# differential_led_board.net
KiCad netlist of a schematic drawn in EAGLE
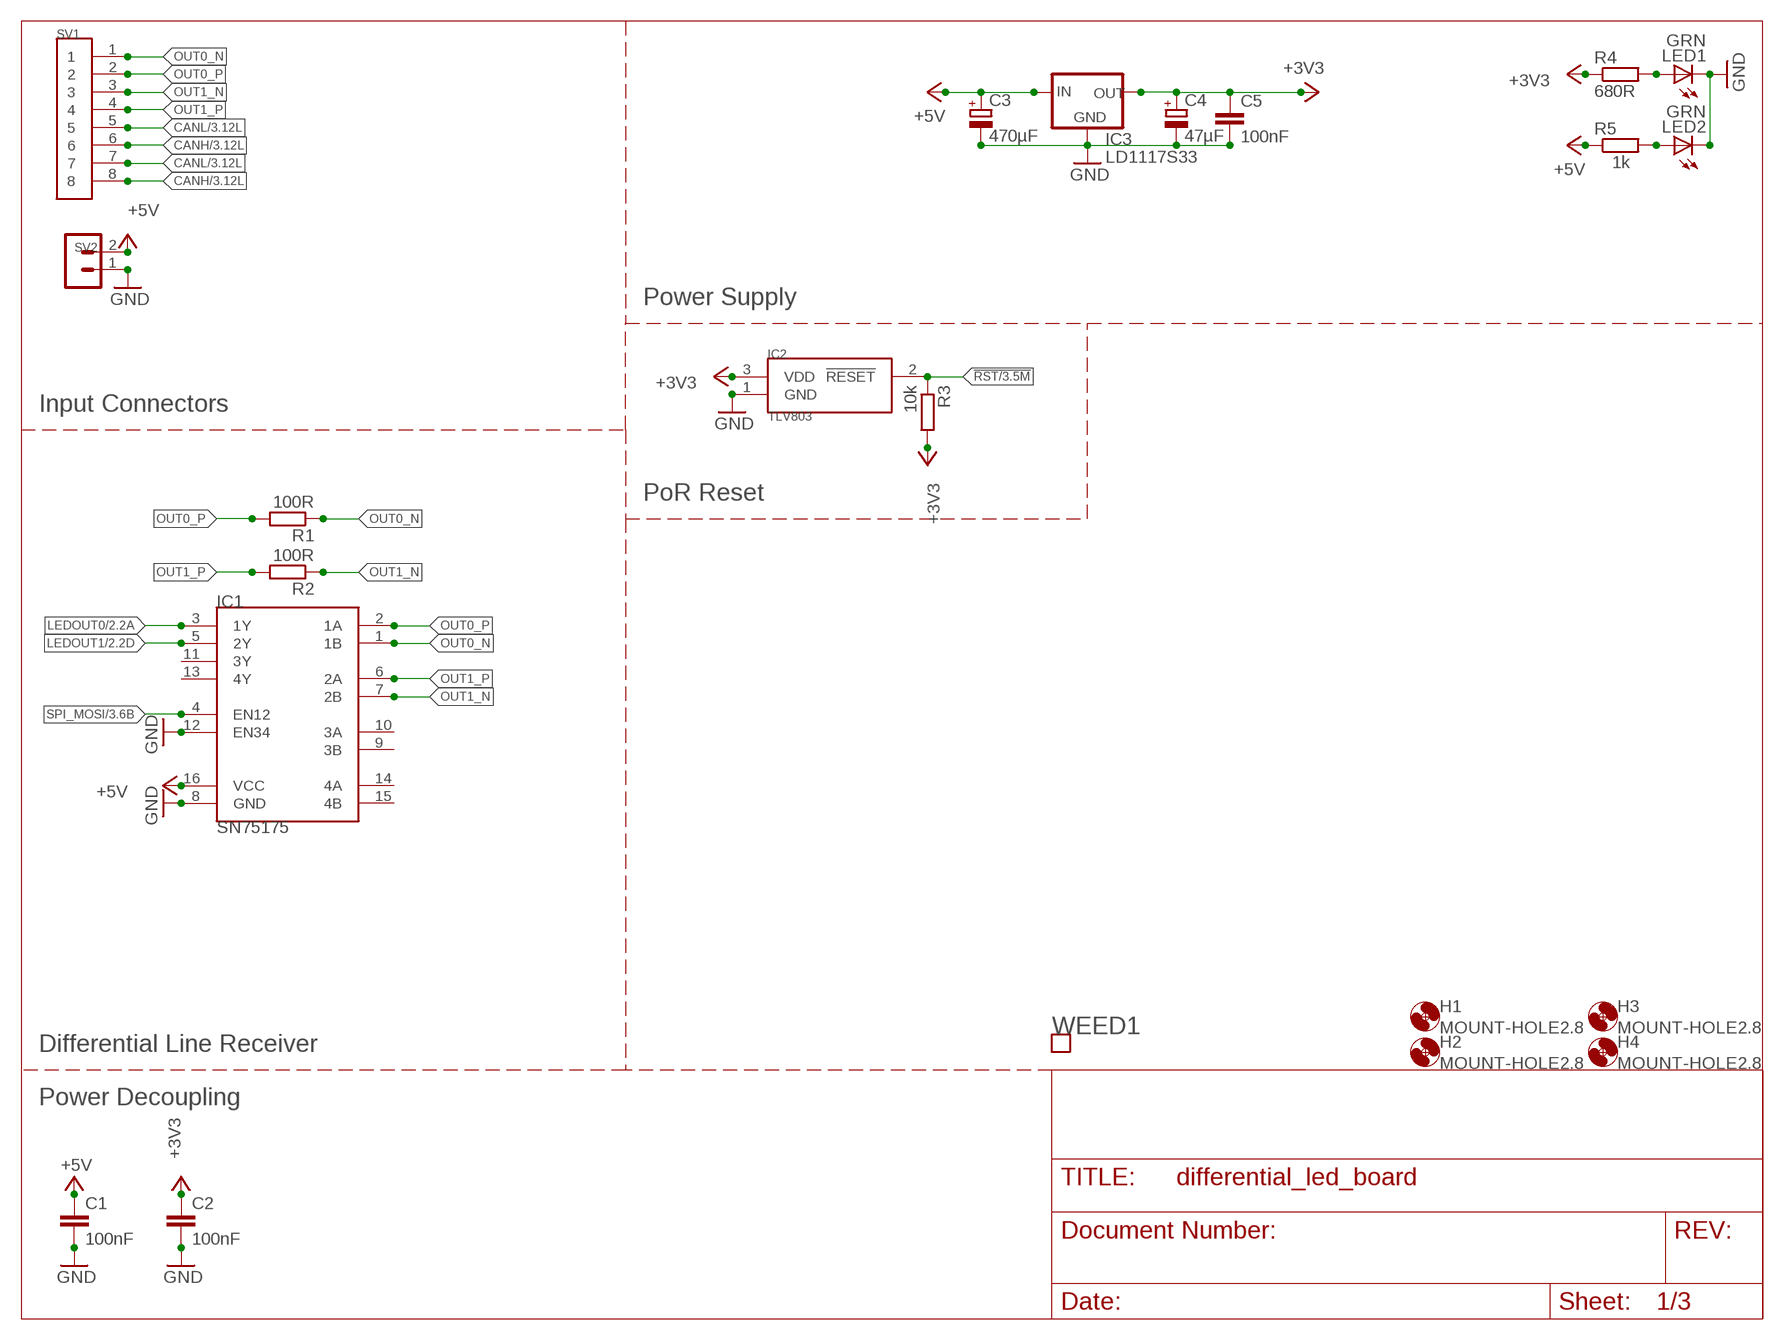
[diagram p0: schematic, sheet 1]
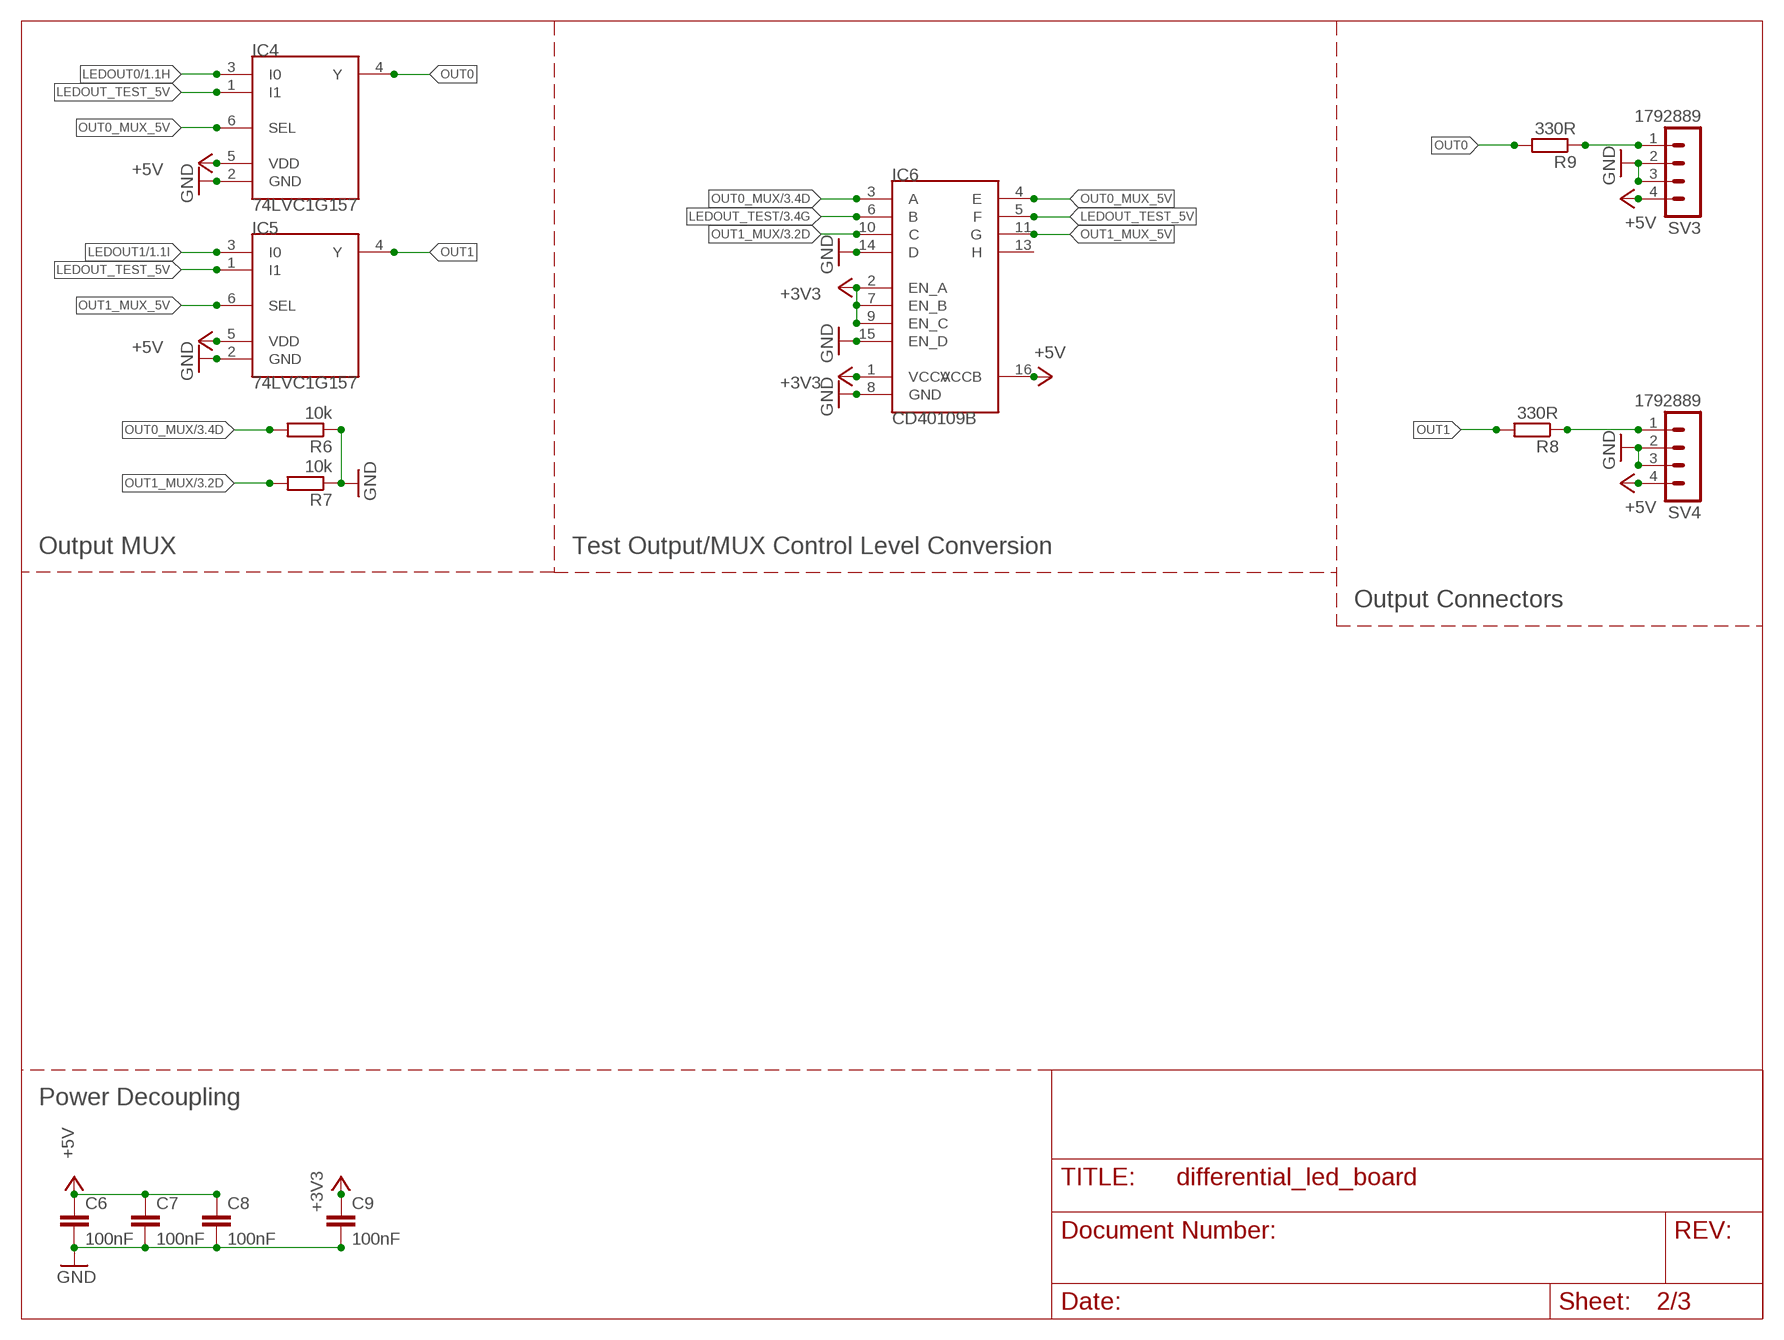
[diagram p1: schematic, sheet 2]
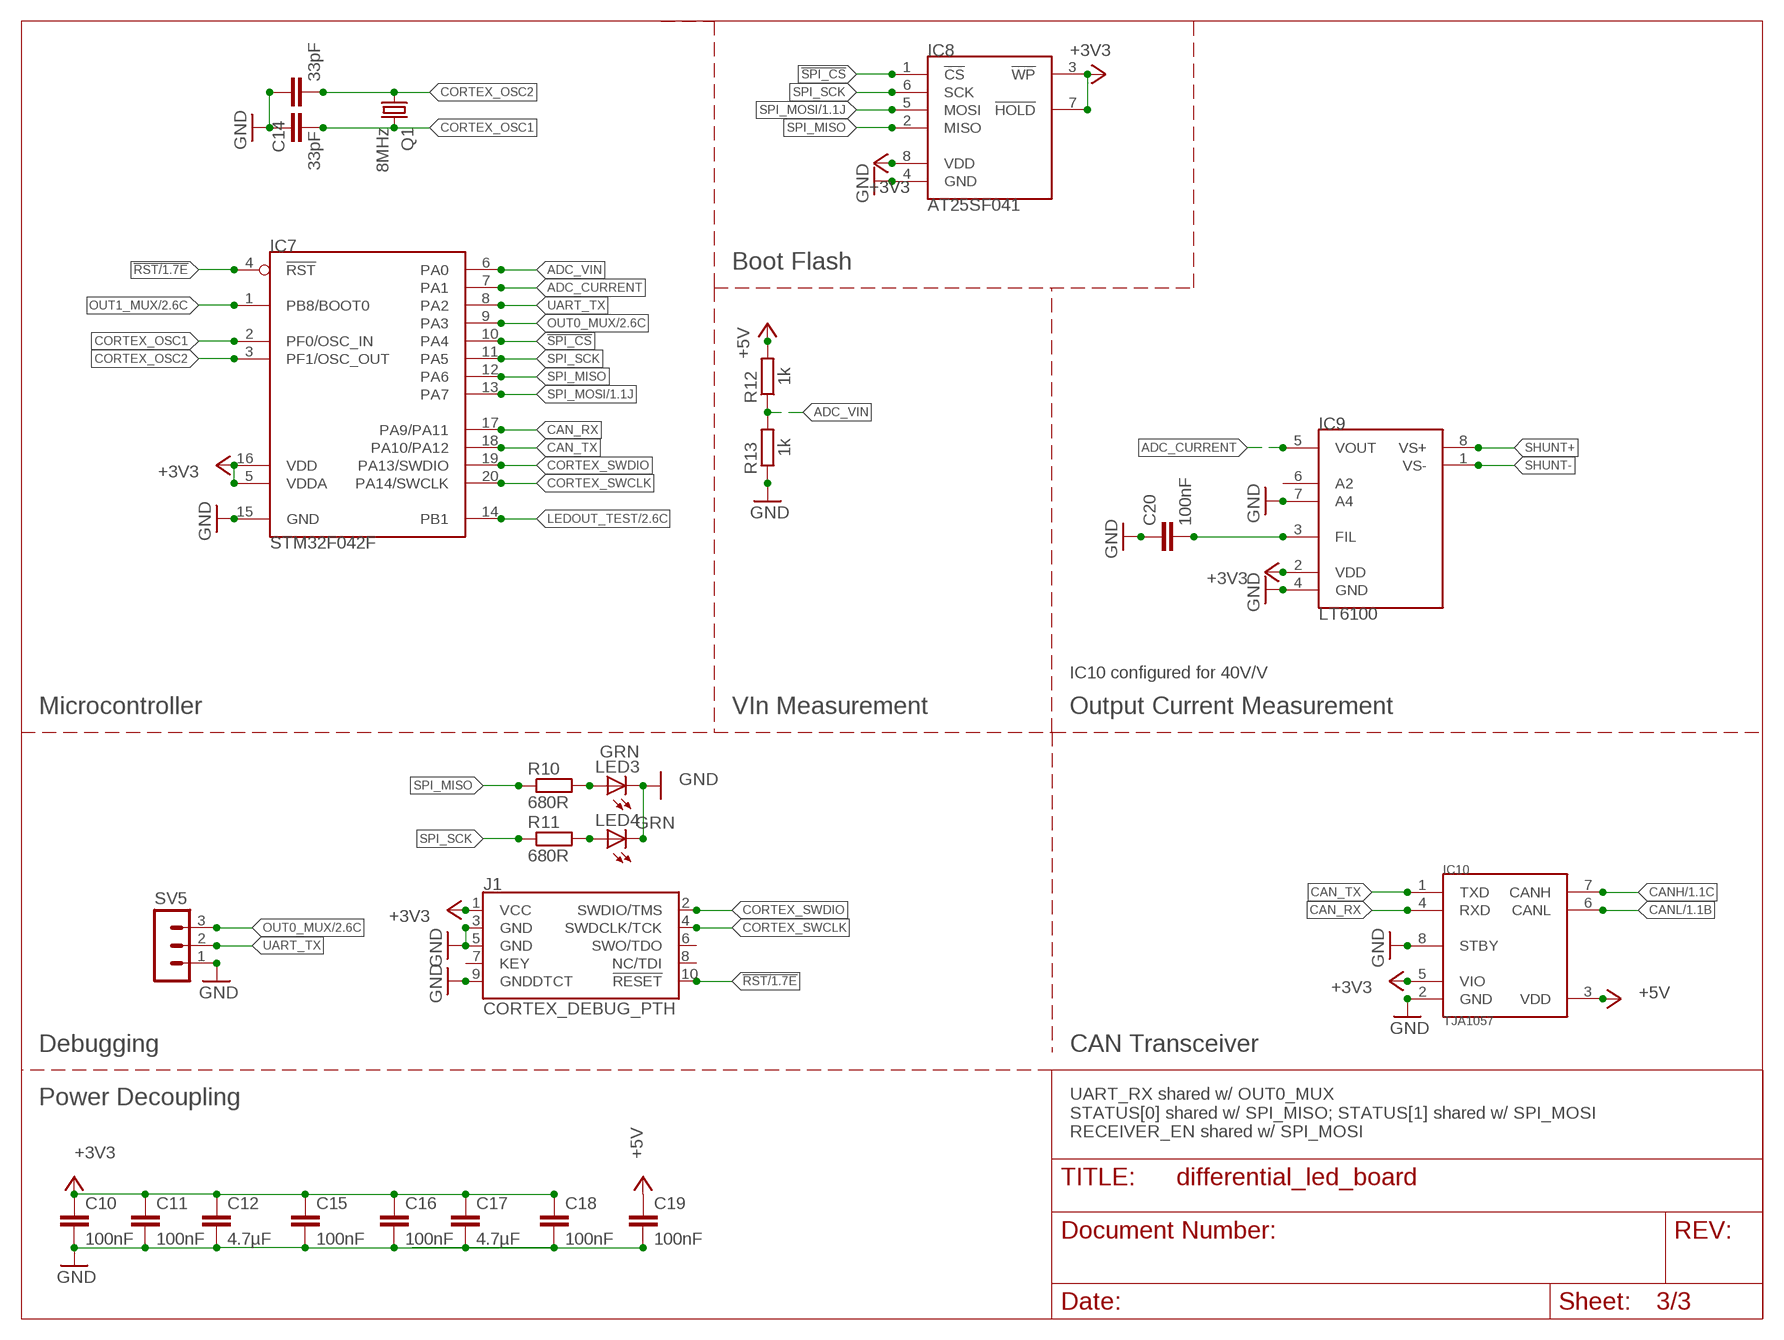
[diagram p2: schematic, sheet 3]

(export (version "E")
  (design (tool "Eeschema 10.0.6"))
  (components
    (comp (ref "C1")
      (value "100nF")
      (footprint "eagle-import:C0805")
      (libsource (lib "eagle-import") (part "C-EUC0805"))
    )
    (comp (ref "C2")
      (value "100nF")
      (footprint "eagle-import:C0805")
      (libsource (lib "eagle-import") (part "C-EUC0805"))
    )
    (comp (ref "C3")
      (value "470µF")
      (footprint "eagle-import:UD-8X10_NICHICON")
      (libsource (lib "eagle-import") (part "CPOL-EUUD-8X10"))
    )
    (comp (ref "C4")
      (value "47µF")
      (footprint "eagle-import:CT6032")
      (libsource (lib "eagle-import") (part "CPOL-EUCT6032"))
    )
    (comp (ref "C5")
      (value "100nF")
      (footprint "eagle-import:C0805")
      (libsource (lib "eagle-import") (part "C-EUC0805"))
    )
    (comp (ref "H1")
      (value "MOUNT-HOLE2.8")
      (footprint "eagle-import:2,8")
      (libsource (lib "eagle-import") (part "MOUNT-HOLE2.8"))
    )
    (comp (ref "H2")
      (value "MOUNT-HOLE2.8")
      (footprint "eagle-import:2,8")
      (libsource (lib "eagle-import") (part "MOUNT-HOLE2.8"))
    )
    (comp (ref "H3")
      (value "MOUNT-HOLE2.8")
      (footprint "eagle-import:2,8")
      (libsource (lib "eagle-import") (part "MOUNT-HOLE2.8"))
    )
    (comp (ref "H4")
      (value "MOUNT-HOLE2.8")
      (footprint "eagle-import:2,8")
      (libsource (lib "eagle-import") (part "MOUNT-HOLE2.8"))
    )
    (comp (ref "IC1")
      (value "SN75175")
      (footprint "eagle-import:SOP-16")
      (libsource (lib "eagle-import") (part "SN75175SOP-16"))
    )
    (comp (ref "IC2")
      (value "TLV803")
      (footprint "eagle-import:SOT23")
      (libsource (lib "eagle-import") (part "TLV803SOT-23"))
    )
    (comp (ref "IC3")
      (value "LD1117S33")
      (footprint "eagle-import:SOT223")
      (libsource (lib "eagle-import") (part "LM1117SOT223"))
    )
    (comp (ref "LED1")
      (value "GRN")
      (footprint "eagle-import:CHIPLED_1206")
      (libsource (lib "eagle-import") (part "LEDCHIPLED_1206"))
    )
    (comp (ref "LED2")
      (value "GRN")
      (footprint "eagle-import:CHIPLED_1206")
      (libsource (lib "eagle-import") (part "LEDCHIPLED_1206"))
    )
    (comp (ref "R1")
      (value "100R")
      (footprint "eagle-import:M1206")
      (libsource (lib "eagle-import") (part "R-EU_M1206"))
    )
    (comp (ref "R2")
      (value "100R")
      (footprint "eagle-import:M1206")
      (libsource (lib "eagle-import") (part "R-EU_M1206"))
    )
    (comp (ref "R3")
      (value "10k")
      (footprint "eagle-import:M0805")
      (libsource (lib "eagle-import") (part "R-EU_M0805"))
    )
    (comp (ref "R4")
      (value "680R")
      (footprint "eagle-import:M0805")
      (libsource (lib "eagle-import") (part "R-EU_M0805"))
    )
    (comp (ref "R5")
      (value "1k")
      (footprint "eagle-import:M0805")
      (libsource (lib "eagle-import") (part "R-EU_M0805"))
    )
    (comp (ref "SV1")
      (value "SS-51000-003")
      (footprint "eagle-import:SS-51000-003")
      (libsource (lib "eagle-import") (part "SS-51000-003"))
    )
    (comp (ref "SV2")
      (value "1792863")
      (footprint "eagle-import:1792863")
      (libsource (lib "eagle-import") (part "1792863"))
    )
    (comp (ref "WEED1")
      (value "WEED")
      (footprint "eagle-import:DOINK")
      (libsource (lib "eagle-import") (part "WEED"))
    )
    (comp (ref "C10")
      (value "100nF")
      (footprint "eagle-import:C0805")
      (libsource (lib "eagle-import") (part "C-EUC0805"))
    )
    (comp (ref "C11")
      (value "100nF")
      (footprint "eagle-import:C0805")
      (libsource (lib "eagle-import") (part "C-EUC0805"))
    )
    (comp (ref "C12")
      (value "4.7µF")
      (footprint "eagle-import:C0805")
      (libsource (lib "eagle-import") (part "C-EUC0805"))
    )
    (comp (ref "C13")
      (value "33pF")
      (footprint "eagle-import:C0805")
      (libsource (lib "eagle-import") (part "C-EUC0805"))
    )
    (comp (ref "C14")
      (value "33pF")
      (footprint "eagle-import:C0805")
      (libsource (lib "eagle-import") (part "C-EUC0805"))
    )
    (comp (ref "C15")
      (value "100nF")
      (footprint "eagle-import:C0805")
      (libsource (lib "eagle-import") (part "C-EUC0805"))
    )
    (comp (ref "C16")
      (value "100nF")
      (footprint "eagle-import:C0805")
      (libsource (lib "eagle-import") (part "C-EUC0805"))
    )
    (comp (ref "C17")
      (value "4.7µF")
      (footprint "eagle-import:C0805")
      (libsource (lib "eagle-import") (part "C-EUC0805"))
    )
    (comp (ref "C18")
      (value "100nF")
      (footprint "eagle-import:C0805")
      (libsource (lib "eagle-import") (part "C-EUC0805"))
    )
    (comp (ref "C19")
      (value "100nF")
      (footprint "eagle-import:C0805")
      (libsource (lib "eagle-import") (part "C-EUC0805"))
    )
    (comp (ref "C20")
      (value "100nF")
      (footprint "eagle-import:C0805")
      (libsource (lib "eagle-import") (part "C-EUC0805"))
    )
    (comp (ref "IC7")
      (value "STM32F042F")
      (footprint "eagle-import:TSSOP20")
      (libsource (lib "eagle-import") (part "STM32F042F"))
    )
    (comp (ref "IC8")
      (value "AT25SF041")
      (footprint "eagle-import:SOIC8")
      (libsource (lib "eagle-import") (part "AT25SF041"))
    )
    (comp (ref "IC9")
      (value "LT6100")
      (footprint "eagle-import:MSOP8")
      (libsource (lib "eagle-import") (part "LT6100MSOP-8"))
    )
    (comp (ref "IC10")
      (value "TJA1057")
      (footprint "eagle-import:SOIC8")
      (libsource (lib "eagle-import") (part "TJA1057"))
    )
    (comp (ref "J1")
      (value "CORTEX_DEBUG_PTH")
      (footprint "eagle-import:2X5-PTH-1.27MM")
      (libsource (lib "eagle-import") (part "CORTEX_DEBUG_PTH"))
    )
    (comp (ref "LED3")
      (value "GRN")
      (footprint "eagle-import:CHIPLED_1206")
      (libsource (lib "eagle-import") (part "LEDCHIPLED_1206"))
    )
    (comp (ref "LED4")
      (value "GRN")
      (footprint "eagle-import:CHIPLED_1206")
      (libsource (lib "eagle-import") (part "LEDCHIPLED_1206"))
    )
    (comp (ref "Q1")
      (value "8MHz")
      (footprint "eagle-import:HC49UP")
      (libsource (lib "eagle-import") (part "CRYSTALHC49UP"))
    )
    (comp (ref "R10")
      (value "680R")
      (footprint "eagle-import:M0805")
      (libsource (lib "eagle-import") (part "R-EU_M0805"))
    )
    (comp (ref "R11")
      (value "680R")
      (footprint "eagle-import:M0805")
      (libsource (lib "eagle-import") (part "R-EU_M0805"))
    )
    (comp (ref "R12")
      (value "1k")
      (footprint "eagle-import:M0805")
      (libsource (lib "eagle-import") (part "R-EU_M0805"))
    )
    (comp (ref "R13")
      (value "1k")
      (footprint "eagle-import:M0805")
      (libsource (lib "eagle-import") (part "R-EU_M0805"))
    )
    (comp (ref "SV5")
      (value "MA03-1")
      (footprint "eagle-import:MA03-1")
      (libsource (lib "eagle-import") (part "MA03-1"))
    )
    (comp (ref "C6")
      (value "100nF")
      (footprint "eagle-import:C0805")
      (libsource (lib "eagle-import") (part "C-EUC0805"))
    )
    (comp (ref "C7")
      (value "100nF")
      (footprint "eagle-import:C0805")
      (libsource (lib "eagle-import") (part "C-EUC0805"))
    )
    (comp (ref "C8")
      (value "100nF")
      (footprint "eagle-import:C0805")
      (libsource (lib "eagle-import") (part "C-EUC0805"))
    )
    (comp (ref "C9")
      (value "100nF")
      (footprint "eagle-import:C0805")
      (libsource (lib "eagle-import") (part "C-EUC0805"))
    )
    (comp (ref "IC4")
      (value "74LVC1G157")
      (footprint "eagle-import:SOT457R_PHILIPS")
      (libsource (lib "eagle-import") (part "74LVC1G157SOT457"))
    )
    (comp (ref "IC5")
      (value "74LVC1G157")
      (footprint "eagle-import:SOT457R_PHILIPS")
      (libsource (lib "eagle-import") (part "74LVC1G157SOT457"))
    )
    (comp (ref "IC6")
      (value "CD40109B")
      (footprint "eagle-import:SO16")
      (libsource (lib "eagle-import") (part "CD40109BSO-16"))
    )
    (comp (ref "R6")
      (value "10k")
      (footprint "eagle-import:M0805")
      (libsource (lib "eagle-import") (part "R-EU_M0805"))
    )
    (comp (ref "R7")
      (value "10k")
      (footprint "eagle-import:M0805")
      (libsource (lib "eagle-import") (part "R-EU_M0805"))
    )
    (comp (ref "R8")
      (value "330R")
      (footprint "eagle-import:M0805")
      (libsource (lib "eagle-import") (part "R-EU_M0805"))
    )
    (comp (ref "R9")
      (value "330R")
      (footprint "eagle-import:M0805")
      (libsource (lib "eagle-import") (part "R-EU_M0805"))
    )
    (comp (ref "SV3")
      (value "1792889")
      (footprint "eagle-import:1792889")
      (libsource (lib "eagle-import") (part "1792889"))
    )
    (comp (ref "SV4")
      (value "1792889")
      (footprint "eagle-import:1792889")
      (libsource (lib "eagle-import") (part "1792889"))
    )
  )
  (nets
    (net (code "1") (name "+3V3") (class "Default")
      (node (ref "C10") (pin "1") (pinfunction "1_1") (pintype "passive"))
      (node (ref "C11") (pin "1") (pinfunction "1_1") (pintype "passive"))
      (node (ref "C12") (pin "1") (pinfunction "1_1") (pintype "passive"))
      (node (ref "C15") (pin "1") (pinfunction "1_1") (pintype "passive"))
      (node (ref "C16") (pin "1") (pinfunction "1_1") (pintype "passive"))
      (node (ref "C17") (pin "1") (pinfunction "1_1") (pintype "passive"))
      (node (ref "C18") (pin "1") (pinfunction "1_1") (pintype "passive"))
      (node (ref "C2") (pin "1") (pinfunction "1_1") (pintype "passive"))
      (node (ref "C4") (pin "+") (pinfunction "+_+") (pintype "passive"))
      (node (ref "C5") (pin "1") (pinfunction "1_1") (pintype "passive"))
      (node (ref "C9") (pin "1") (pinfunction "1_1") (pintype "passive"))
      (node (ref "IC10") (pin "5") (pinfunction "VIO_5") (pintype "bidirectional"))
      (node (ref "IC2") (pin "3") (pinfunction "VDD_3") (pintype "power_in"))
      (node (ref "IC3") (pin "2") (pinfunction "OUT_2") (pintype "output"))
      (node (ref "IC3") (pin "4") (pinfunction "OUT_4") (pintype "output"))
      (node (ref "IC6") (pin "1") (pinfunction "VCCA_1") (pintype "bidirectional"))
      (node (ref "IC6") (pin "2") (pinfunction "EN_A_2") (pintype "bidirectional"))
      (node (ref "IC6") (pin "7") (pinfunction "EN_B_7") (pintype "bidirectional"))
      (node (ref "IC6") (pin "9") (pinfunction "EN_C_9") (pintype "bidirectional"))
      (node (ref "IC7") (pin "16") (pinfunction "VDD_16") (pintype "power_in"))
      (node (ref "IC7") (pin "5") (pinfunction "VDDA_5") (pintype "power_in"))
      (node (ref "IC8") (pin "3") (pinfunction "~{WP}_3") (pintype "bidirectional"))
      (node (ref "IC8") (pin "7") (pinfunction "~{HOLD}_7") (pintype "bidirectional"))
      (node (ref "IC8") (pin "8") (pinfunction "VDD_8") (pintype "power_in"))
      (node (ref "IC9") (pin "2") (pinfunction "VDD_2") (pintype "power_in"))
      (node (ref "J1") (pin "1") (pinfunction "VCC_1") (pintype "bidirectional"))
      (node (ref "R3") (pin "2") (pinfunction "2_2") (pintype "passive"))
      (node (ref "R4") (pin "1") (pinfunction "1_1") (pintype "passive"))
    )
    (net (code "2") (name "+5V") (class "Default")
      (node (ref "C1") (pin "1") (pinfunction "1_1") (pintype "passive"))
      (node (ref "C19") (pin "1") (pinfunction "1_1") (pintype "passive"))
      (node (ref "C3") (pin "+") (pinfunction "+_+") (pintype "passive"))
      (node (ref "C6") (pin "1") (pinfunction "1_1") (pintype "passive"))
      (node (ref "C7") (pin "1") (pinfunction "1_1") (pintype "passive"))
      (node (ref "C8") (pin "1") (pinfunction "1_1") (pintype "passive"))
      (node (ref "IC1") (pin "16") (pinfunction "VCC_16") (pintype "power_in"))
      (node (ref "IC10") (pin "3") (pinfunction "VDD_3") (pintype "bidirectional"))
      (node (ref "IC3") (pin "3") (pinfunction "IN_3") (pintype "input"))
      (node (ref "IC4") (pin "5") (pinfunction "VDD_5") (pintype "power_in"))
      (node (ref "IC5") (pin "5") (pinfunction "VDD_5") (pintype "power_in"))
      (node (ref "IC6") (pin "16") (pinfunction "VCCB_16") (pintype "bidirectional"))
      (node (ref "R12") (pin "2") (pinfunction "2_2") (pintype "passive"))
      (node (ref "R5") (pin "1") (pinfunction "1_1") (pintype "passive"))
      (node (ref "SV2") (pin "2") (pinfunction "2_2") (pintype "passive"))
      (node (ref "SV3") (pin "4") (pinfunction "4_4") (pintype "passive"))
      (node (ref "SV4") (pin "4") (pinfunction "4_4") (pintype "passive"))
    )
    (net (code "3") (name "ADC_CURRENT") (class "Default")
      (node (ref "IC7") (pin "7") (pinfunction "PA1_7") (pintype "bidirectional"))
      (node (ref "IC9") (pin "5") (pinfunction "VOUT_5") (pintype "bidirectional"))
    )
    (net (code "4") (name "ADC_VIN") (class "Default")
      (node (ref "IC7") (pin "6") (pinfunction "PA0_6") (pintype "bidirectional"))
      (node (ref "R12") (pin "1") (pinfunction "1_1") (pintype "passive"))
      (node (ref "R13") (pin "2") (pinfunction "2_2") (pintype "passive"))
    )
    (net (code "5") (name "CANH") (class "Default")
      (node (ref "IC10") (pin "7") (pinfunction "CANH_7") (pintype "bidirectional"))
      (node (ref "SV1") (pin "6") (pinfunction "6_6") (pintype "passive"))
      (node (ref "SV1") (pin "8") (pinfunction "8_8") (pintype "passive"))
    )
    (net (code "6") (name "CANL") (class "Default")
      (node (ref "IC10") (pin "6") (pinfunction "CANL_6") (pintype "bidirectional"))
      (node (ref "SV1") (pin "5") (pinfunction "5_5") (pintype "passive"))
      (node (ref "SV1") (pin "7") (pinfunction "7_7") (pintype "passive"))
    )
    (net (code "7") (name "CAN_RX") (class "Default")
      (node (ref "IC10") (pin "4") (pinfunction "RXD_4") (pintype "bidirectional"))
      (node (ref "IC7") (pin "17") (pinfunction "PA9/PA11_17") (pintype "bidirectional"))
    )
    (net (code "8") (name "CAN_TX") (class "Default")
      (node (ref "IC10") (pin "1") (pinfunction "TXD_1") (pintype "bidirectional"))
      (node (ref "IC7") (pin "18") (pinfunction "PA10/PA12_18") (pintype "bidirectional"))
    )
    (net (code "9") (name "CORTEX_OSC1") (class "Default")
      (node (ref "C14") (pin "2") (pinfunction "2_2") (pintype "passive"))
      (node (ref "IC7") (pin "2") (pinfunction "PF0/OSC_IN_2") (pintype "bidirectional"))
      (node (ref "Q1") (pin "2") (pinfunction "2_2") (pintype "passive"))
    )
    (net (code "10") (name "CORTEX_OSC2") (class "Default")
      (node (ref "C13") (pin "2") (pinfunction "2_2") (pintype "passive"))
      (node (ref "IC7") (pin "3") (pinfunction "PF1/OSC_OUT_3") (pintype "bidirectional"))
      (node (ref "Q1") (pin "1") (pinfunction "1_1") (pintype "passive"))
    )
    (net (code "11") (name "CORTEX_SWCLK") (class "Default")
      (node (ref "IC7") (pin "20") (pinfunction "PA14/SWCLK_20") (pintype "bidirectional"))
      (node (ref "J1") (pin "4") (pinfunction "SWDCLK/TCK_4") (pintype "bidirectional"))
    )
    (net (code "12") (name "CORTEX_SWDIO") (class "Default")
      (node (ref "IC7") (pin "19") (pinfunction "PA13/SWDIO_19") (pintype "bidirectional"))
      (node (ref "J1") (pin "2") (pinfunction "SWDIO/TMS_2") (pintype "bidirectional"))
    )
    (net (code "13") (name "GND") (class "Default")
      (node (ref "C1") (pin "2") (pinfunction "2_2") (pintype "passive"))
      (node (ref "C10") (pin "2") (pinfunction "2_2") (pintype "passive"))
      (node (ref "C11") (pin "2") (pinfunction "2_2") (pintype "passive"))
      (node (ref "C12") (pin "2") (pinfunction "2_2") (pintype "passive"))
      (node (ref "C13") (pin "1") (pinfunction "1_1") (pintype "passive"))
      (node (ref "C14") (pin "1") (pinfunction "1_1") (pintype "passive"))
      (node (ref "C15") (pin "2") (pinfunction "2_2") (pintype "passive"))
      (node (ref "C16") (pin "2") (pinfunction "2_2") (pintype "passive"))
      (node (ref "C17") (pin "2") (pinfunction "2_2") (pintype "passive"))
      (node (ref "C18") (pin "2") (pinfunction "2_2") (pintype "passive"))
      (node (ref "C19") (pin "2") (pinfunction "2_2") (pintype "passive"))
      (node (ref "C2") (pin "2") (pinfunction "2_2") (pintype "passive"))
      (node (ref "C20") (pin "1") (pinfunction "1_1") (pintype "passive"))
      (node (ref "C3") (pin "-") (pinfunction "-_-") (pintype "passive"))
      (node (ref "C4") (pin "-") (pinfunction "-_-") (pintype "passive"))
      (node (ref "C5") (pin "2") (pinfunction "2_2") (pintype "passive"))
      (node (ref "C6") (pin "2") (pinfunction "2_2") (pintype "passive"))
      (node (ref "C7") (pin "2") (pinfunction "2_2") (pintype "passive"))
      (node (ref "C8") (pin "2") (pinfunction "2_2") (pintype "passive"))
      (node (ref "C9") (pin "2") (pinfunction "2_2") (pintype "passive"))
      (node (ref "IC1") (pin "12") (pinfunction "EN34_12") (pintype "input"))
      (node (ref "IC1") (pin "8") (pinfunction "GND_8") (pintype "power_in"))
      (node (ref "IC10") (pin "2") (pinfunction "GND_2") (pintype "bidirectional"))
      (node (ref "IC10") (pin "8") (pinfunction "STBY_8") (pintype "bidirectional"))
      (node (ref "IC2") (pin "1") (pinfunction "GND_1") (pintype "power_in"))
      (node (ref "IC3") (pin "1") (pinfunction "GND_1") (pintype "input"))
      (node (ref "IC4") (pin "2") (pinfunction "GND_2") (pintype "power_in"))
      (node (ref "IC5") (pin "2") (pinfunction "GND_2") (pintype "power_in"))
      (node (ref "IC6") (pin "14") (pinfunction "D_14") (pintype "bidirectional"))
      (node (ref "IC6") (pin "15") (pinfunction "EN_D_15") (pintype "bidirectional"))
      (node (ref "IC6") (pin "8") (pinfunction "GND_8") (pintype "bidirectional"))
      (node (ref "IC7") (pin "15") (pinfunction "GND_15") (pintype "power_in"))
      (node (ref "IC8") (pin "4") (pinfunction "GND_4") (pintype "power_in"))
      (node (ref "IC9") (pin "4") (pinfunction "GND_4") (pintype "power_in"))
      (node (ref "IC9") (pin "7") (pinfunction "A4_7") (pintype "bidirectional"))
      (node (ref "J1") (pin "3") (pinfunction "GND_3") (pintype "bidirectional"))
      (node (ref "J1") (pin "5") (pinfunction "GND_5") (pintype "bidirectional"))
      (node (ref "J1") (pin "9") (pinfunction "GNDDTCT_9") (pintype "bidirectional"))
      (node (ref "LED1") (pin "C") (pinfunction "C_C") (pintype "passive"))
      (node (ref "LED2") (pin "C") (pinfunction "C_C") (pintype "passive"))
      (node (ref "LED3") (pin "C") (pinfunction "C_C") (pintype "passive"))
      (node (ref "LED4") (pin "C") (pinfunction "C_C") (pintype "passive"))
      (node (ref "R13") (pin "1") (pinfunction "1_1") (pintype "passive"))
      (node (ref "R6") (pin "1") (pinfunction "1_1") (pintype "passive"))
      (node (ref "R7") (pin "1") (pinfunction "1_1") (pintype "passive"))
      (node (ref "SV2") (pin "1") (pinfunction "1_1") (pintype "passive"))
      (node (ref "SV3") (pin "2") (pinfunction "2_2") (pintype "passive"))
      (node (ref "SV3") (pin "3") (pinfunction "3_3") (pintype "passive"))
      (node (ref "SV4") (pin "2") (pinfunction "2_2") (pintype "passive"))
      (node (ref "SV4") (pin "3") (pinfunction "3_3") (pintype "passive"))
      (node (ref "SV5") (pin "1") (pinfunction "1_1") (pintype "passive"))
    )
    (net (code "14") (name "LEDOUT0") (class "Default")
      (node (ref "IC1") (pin "3") (pinfunction "1Y_3") (pintype "output"))
      (node (ref "IC4") (pin "3") (pinfunction "I0_3") (pintype "input"))
    )
    (net (code "15") (name "LEDOUT1") (class "Default")
      (node (ref "IC1") (pin "5") (pinfunction "2Y_5") (pintype "output"))
      (node (ref "IC5") (pin "3") (pinfunction "I0_3") (pintype "input"))
    )
    (net (code "16") (name "LEDOUT_TEST") (class "Default")
      (node (ref "IC6") (pin "6") (pinfunction "B_6") (pintype "bidirectional"))
      (node (ref "IC7") (pin "14") (pinfunction "PB1_14") (pintype "bidirectional"))
    )
    (net (code "17") (name "LEDOUT_TEST_5V") (class "Default")
      (node (ref "IC4") (pin "1") (pinfunction "I1_1") (pintype "input"))
      (node (ref "IC5") (pin "1") (pinfunction "I1_1") (pintype "input"))
      (node (ref "IC6") (pin "5") (pinfunction "F_5") (pintype "bidirectional"))
    )
    (net (code "18") (name "Net-(IC9-FIL)") (class "Default")
      (node (ref "C20") (pin "2") (pinfunction "2_2") (pintype "passive"))
      (node (ref "IC9") (pin "3") (pinfunction "FIL_3") (pintype "bidirectional"))
    )
    (net (code "19") (name "Net-(LED1-PadA)") (class "Default")
      (node (ref "LED1") (pin "A") (pinfunction "A_A") (pintype "passive"))
      (node (ref "R4") (pin "2") (pinfunction "2_2") (pintype "passive"))
    )
    (net (code "20") (name "Net-(LED2-PadA)") (class "Default")
      (node (ref "LED2") (pin "A") (pinfunction "A_A") (pintype "passive"))
      (node (ref "R5") (pin "2") (pinfunction "2_2") (pintype "passive"))
    )
    (net (code "21") (name "Net-(LED3-PadA)") (class "Default")
      (node (ref "LED3") (pin "A") (pinfunction "A_A") (pintype "passive"))
      (node (ref "R10") (pin "2") (pinfunction "2_2") (pintype "passive"))
    )
    (net (code "22") (name "Net-(LED4-PadA)") (class "Default")
      (node (ref "LED4") (pin "A") (pinfunction "A_A") (pintype "passive"))
      (node (ref "R11") (pin "2") (pinfunction "2_2") (pintype "passive"))
    )
    (net (code "23") (name "Net-(R8-Pad1)") (class "Default")
      (node (ref "R8") (pin "1") (pinfunction "1_1") (pintype "passive"))
      (node (ref "SV4") (pin "1") (pinfunction "1_1") (pintype "passive"))
    )
    (net (code "24") (name "Net-(R9-Pad1)") (class "Default")
      (node (ref "R9") (pin "1") (pinfunction "1_1") (pintype "passive"))
      (node (ref "SV3") (pin "1") (pinfunction "1_1") (pintype "passive"))
    )
    (net (code "25") (name "OUT0") (class "Default")
      (node (ref "IC4") (pin "4") (pinfunction "Y_4") (pintype "output"))
      (node (ref "R9") (pin "2") (pinfunction "2_2") (pintype "passive"))
    )
    (net (code "26") (name "OUT0_MUX") (class "Default")
      (node (ref "IC6") (pin "3") (pinfunction "A_3") (pintype "bidirectional"))
      (node (ref "IC7") (pin "9") (pinfunction "PA3_9") (pintype "bidirectional"))
      (node (ref "R6") (pin "2") (pinfunction "2_2") (pintype "passive"))
      (node (ref "SV5") (pin "3") (pinfunction "3_3") (pintype "passive"))
    )
    (net (code "27") (name "OUT0_MUX_5V") (class "Default")
      (node (ref "IC4") (pin "6") (pinfunction "SEL_6") (pintype "input"))
      (node (ref "IC6") (pin "4") (pinfunction "E_4") (pintype "bidirectional"))
    )
    (net (code "28") (name "OUT0_N") (class "Default")
      (node (ref "IC1") (pin "1") (pinfunction "1B_1") (pintype "bidirectional"))
      (node (ref "R1") (pin "1") (pinfunction "1_1") (pintype "passive"))
      (node (ref "SV1") (pin "1") (pinfunction "1_1") (pintype "passive"))
    )
    (net (code "29") (name "OUT0_P") (class "Default")
      (node (ref "IC1") (pin "2") (pinfunction "1A_2") (pintype "bidirectional"))
      (node (ref "R1") (pin "2") (pinfunction "2_2") (pintype "passive"))
      (node (ref "SV1") (pin "2") (pinfunction "2_2") (pintype "passive"))
    )
    (net (code "30") (name "OUT1") (class "Default")
      (node (ref "IC5") (pin "4") (pinfunction "Y_4") (pintype "output"))
      (node (ref "R8") (pin "2") (pinfunction "2_2") (pintype "passive"))
    )
    (net (code "31") (name "OUT1_MUX") (class "Default")
      (node (ref "IC6") (pin "10") (pinfunction "C_10") (pintype "bidirectional"))
      (node (ref "IC7") (pin "1") (pinfunction "PB8/BOOT0_1") (pintype "bidirectional"))
      (node (ref "R7") (pin "2") (pinfunction "2_2") (pintype "passive"))
    )
    (net (code "32") (name "OUT1_MUX_5V") (class "Default")
      (node (ref "IC5") (pin "6") (pinfunction "SEL_6") (pintype "input"))
      (node (ref "IC6") (pin "11") (pinfunction "G_11") (pintype "bidirectional"))
    )
    (net (code "33") (name "OUT1_N") (class "Default")
      (node (ref "IC1") (pin "7") (pinfunction "2B_7") (pintype "bidirectional"))
      (node (ref "R2") (pin "1") (pinfunction "1_1") (pintype "passive"))
      (node (ref "SV1") (pin "3") (pinfunction "3_3") (pintype "passive"))
    )
    (net (code "34") (name "OUT1_P") (class "Default")
      (node (ref "IC1") (pin "6") (pinfunction "2A_6") (pintype "bidirectional"))
      (node (ref "R2") (pin "2") (pinfunction "2_2") (pintype "passive"))
      (node (ref "SV1") (pin "4") (pinfunction "4_4") (pintype "passive"))
    )
    (net (code "35") (name "SHUNT+") (class "Default")
      (node (ref "IC9") (pin "8") (pinfunction "VS+_8") (pintype "bidirectional"))
    )
    (net (code "36") (name "SHUNT-") (class "Default")
      (node (ref "IC9") (pin "1") (pinfunction "VS-_1") (pintype "bidirectional"))
    )
    (net (code "37") (name "SPI_MISO") (class "Default")
      (node (ref "IC7") (pin "12") (pinfunction "PA6_12") (pintype "bidirectional"))
      (node (ref "IC8") (pin "2") (pinfunction "MISO_2") (pintype "bidirectional"))
      (node (ref "R10") (pin "1") (pinfunction "1_1") (pintype "passive"))
    )
    (net (code "38") (name "SPI_MOSI") (class "Default")
      (node (ref "IC1") (pin "4") (pinfunction "EN12_4") (pintype "input"))
      (node (ref "IC7") (pin "13") (pinfunction "PA7_13") (pintype "bidirectional"))
      (node (ref "IC8") (pin "5") (pinfunction "MOSI_5") (pintype "bidirectional"))
    )
    (net (code "39") (name "SPI_SCK") (class "Default")
      (node (ref "IC7") (pin "11") (pinfunction "PA5_11") (pintype "bidirectional"))
      (node (ref "IC8") (pin "6") (pinfunction "SCK_6") (pintype "bidirectional"))
      (node (ref "R11") (pin "1") (pinfunction "1_1") (pintype "passive"))
    )
    (net (code "40") (name "UART_TX") (class "Default")
      (node (ref "IC7") (pin "8") (pinfunction "PA2_8") (pintype "bidirectional"))
      (node (ref "SV5") (pin "2") (pinfunction "2_2") (pintype "passive"))
    )
    (net (code "41") (name "unconnected-(IC1-3A-Pad10)") (class "Default")
      (node (ref "IC1") (pin "10") (pinfunction "3A_10") (pintype "bidirectional"))
    )
    (net (code "42") (name "unconnected-(IC1-3B-Pad9)") (class "Default")
      (node (ref "IC1") (pin "9") (pinfunction "3B_9") (pintype "bidirectional"))
    )
    (net (code "43") (name "unconnected-(IC1-3Y-Pad11)") (class "Default")
      (node (ref "IC1") (pin "11") (pinfunction "3Y_11") (pintype "output"))
    )
    (net (code "44") (name "unconnected-(IC1-4A-Pad14)") (class "Default")
      (node (ref "IC1") (pin "14") (pinfunction "4A_14") (pintype "bidirectional"))
    )
    (net (code "45") (name "unconnected-(IC1-4B-Pad15)") (class "Default")
      (node (ref "IC1") (pin "15") (pinfunction "4B_15") (pintype "bidirectional"))
    )
    (net (code "46") (name "unconnected-(IC1-4Y-Pad13)") (class "Default")
      (node (ref "IC1") (pin "13") (pinfunction "4Y_13") (pintype "output"))
    )
    (net (code "47") (name "unconnected-(IC6-H-Pad13)") (class "Default")
      (node (ref "IC6") (pin "13") (pinfunction "H_13") (pintype "bidirectional"))
    )
    (net (code "48") (name "unconnected-(IC9-A2-Pad6)") (class "Default")
      (node (ref "IC9") (pin "6") (pinfunction "A2_6") (pintype "bidirectional"))
    )
    (net (code "49") (name "unconnected-(J1-KEY-Pad7)") (class "Default")
      (node (ref "J1") (pin "7") (pinfunction "KEY_7") (pintype "bidirectional"))
    )
    (net (code "50") (name "unconnected-(J1-NC{slash}TDI-Pad8)") (class "Default")
      (node (ref "J1") (pin "8") (pinfunction "NC/TDI_8") (pintype "bidirectional"))
    )
    (net (code "51") (name "unconnected-(J1-SWO{slash}TDO-Pad6)") (class "Default")
      (node (ref "J1") (pin "6") (pinfunction "SWO/TDO_6") (pintype "bidirectional"))
    )
    (net (code "52") (name "~{RST}") (class "Default")
      (node (ref "IC2") (pin "2") (pinfunction "~{RESET}_2") (pintype "bidirectional"))
      (node (ref "IC7") (pin "4") (pinfunction "~{RST}_4") (pintype "input"))
      (node (ref "J1") (pin "10") (pinfunction "~{RESET}_10") (pintype "bidirectional"))
      (node (ref "R3") (pin "1") (pinfunction "1_1") (pintype "passive"))
    )
    (net (code "53") (name "~{SPI_CS}") (class "Default")
      (node (ref "IC7") (pin "10") (pinfunction "PA4_10") (pintype "bidirectional"))
      (node (ref "IC8") (pin "1") (pinfunction "~{CS}_1") (pintype "bidirectional"))
    )
  )
)
